# 60-hv-amp-interlock.net
KiCad netlist of a schematic drawn in EAGLE
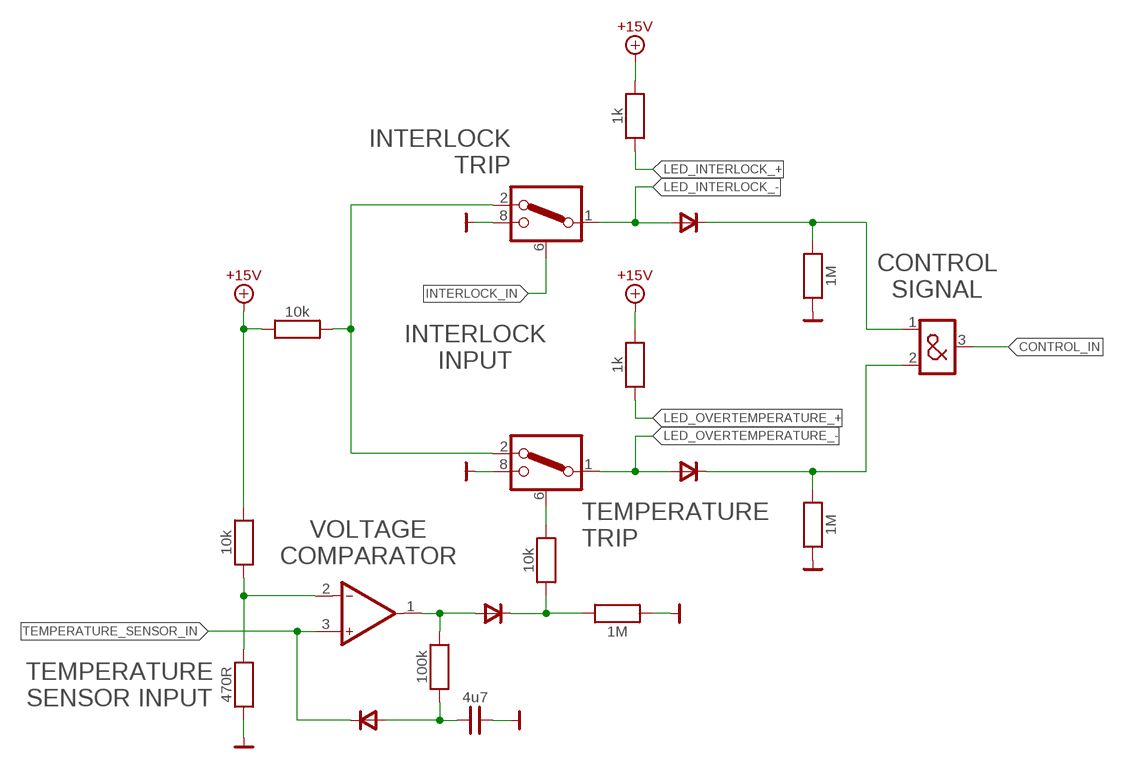
[diagram p0: schematic, sheet 1]

(export (version "E")
  (design (tool "Eeschema 10.0.6"))
  (components
    (comp (ref "C21")
      (value "4u7")
      (footprint "eagle-import:C02-MKS2-7.0-N")
      (libsource (lib "eagle-import") (part "C02-MKS2-7.0-N"))
    )
    (comp (ref "D17")
      (value "1N4148")
      (footprint "eagle-import:D04N-DO35-TYPE")
      (libsource (lib "eagle-import") (part "1N4148-04"))
    )
    (comp (ref "D21")
      (value "1N4148")
      (footprint "eagle-import:D04N-DO35-TYPE")
      (libsource (lib "eagle-import") (part "1N4148-04"))
    )
    (comp (ref "D25")
      (value "1N4148")
      (footprint "eagle-import:D04N-DO35-TYPE")
      (libsource (lib "eagle-import") (part "1N4148-04"))
    )
    (comp (ref "D26")
      (value "1N4148")
      (footprint "eagle-import:D04N-DO35-TYPE")
      (libsource (lib "eagle-import") (part "1N4148-04"))
    )
    (comp (ref "N21")
      (value "OPA4277")
      (footprint "eagle-import:DIP14L")
      (libsource (lib "eagle-import") (part "OPA4277L"))
    )
    (comp (ref "N22")
      (value "MAX4659")
      (footprint "eagle-import:DIP08L")
      (libsource (lib "eagle-import") (part "DG419L"))
    )
    (comp (ref "N23")
      (value "MAX4659")
      (footprint "eagle-import:DIP08L")
      (libsource (lib "eagle-import") (part "DG419L"))
    )
    (comp (ref "N24")
      (value "4081")
      (footprint "eagle-import:DIP14L")
      (libsource (lib "eagle-import") (part "4081L"))
    )
    (comp (ref "R1")
      (value "1M")
      (footprint "eagle-import:R04N")
      (libsource (lib "eagle-import") (part "R04"))
    )
    (comp (ref "R97")
      (value "10k")
      (footprint "eagle-import:R04N")
      (libsource (lib "eagle-import") (part "RN"))
    )
    (comp (ref "R98")
      (value "470R")
      (footprint "eagle-import:R04N")
      (libsource (lib "eagle-import") (part "RN"))
    )
    (comp (ref "R105")
      (value "100k")
      (footprint "eagle-import:R04N")
      (libsource (lib "eagle-import") (part "RN"))
    )
    (comp (ref "R109")
      (value "10k")
      (footprint "eagle-import:R04N")
      (libsource (lib "eagle-import") (part "R04"))
    )
    (comp (ref "R110")
      (value "10k")
      (footprint "eagle-import:R04N")
      (libsource (lib "eagle-import") (part "RN"))
    )
    (comp (ref "R111")
      (value "1k")
      (footprint "eagle-import:R04N")
      (libsource (lib "eagle-import") (part "R04"))
    )
    (comp (ref "R112")
      (value "1k")
      (footprint "eagle-import:R04N")
      (libsource (lib "eagle-import") (part "R04"))
    )
    (comp (ref "R150")
      (value "1M")
      (footprint "eagle-import:R04N")
      (libsource (lib "eagle-import") (part "R04"))
    )
    (comp (ref "R151")
      (value "1M")
      (footprint "eagle-import:R04N")
      (libsource (lib "eagle-import") (part "R04"))
    )
  )
  (nets
    (net (code "1") (name "CONTROL_IN") (class "Default")
      (node (ref "N24") (pin "3") (pinfunction "O_3") (pintype "output"))
    )
    (net (code "2") (name "INTERLOCK_IN") (class "Default")
      (node (ref "N22") (pin "6") (pinfunction "D_6") (pintype "input"))
    )
    (net (code "3") (name "LED_INTERLOCK_+") (class "Default")
      (node (ref "R111") (pin "1") (pinfunction "1_1") (pintype "passive"))
    )
    (net (code "4") (name "LED_INTERLOCK_-") (class "Default")
      (node (ref "D25") (pin "A") (pinfunction "A_A") (pintype "passive"))
      (node (ref "N22") (pin "1") (pinfunction "S1_1") (pintype "bidirectional"))
    )
    (net (code "5") (name "LED_OVERTEMPERATURE_+") (class "Default")
      (node (ref "R112") (pin "1") (pinfunction "1_1") (pintype "passive"))
    )
    (net (code "6") (name "LED_OVERTEMPERATURE_-") (class "Default")
      (node (ref "D26") (pin "A") (pinfunction "A_A") (pintype "passive"))
      (node (ref "N23") (pin "1") (pinfunction "S1_1") (pintype "bidirectional"))
    )
    (net (code "7") (name "Net-(C21-Pad2)") (class "Default")
      (node (ref "C21") (pin "2") (pinfunction "2_2") (pintype "passive"))
      (node (ref "D17") (pin "A") (pinfunction "A_A") (pintype "passive"))
      (node (ref "R105") (pin "1") (pinfunction "1_1") (pintype "passive"))
    )
    (net (code "8") (name "Net-(D21-PadC)") (class "Default")
      (node (ref "D21") (pin "C") (pinfunction "C_C") (pintype "passive"))
      (node (ref "R1") (pin "2") (pinfunction "2_2") (pintype "passive"))
      (node (ref "R110") (pin "1") (pinfunction "1_1") (pintype "passive"))
    )
    (net (code "9") (name "Net-(N21A-IN-)") (class "Default")
      (node (ref "N21") (pin "2") (pinfunction "IN-_2") (pintype "input"))
      (node (ref "R97") (pin "1") (pinfunction "1_1") (pintype "passive"))
      (node (ref "R98") (pin "2") (pinfunction "2_2") (pintype "passive"))
    )
    (net (code "10") (name "Net-(N21A-OUT)") (class "Default")
      (node (ref "D21") (pin "A") (pinfunction "A_A") (pintype "passive"))
      (node (ref "N21") (pin "1") (pinfunction "OUT_1") (pintype "output"))
      (node (ref "R105") (pin "2") (pinfunction "2_2") (pintype "passive"))
    )
    (net (code "11") (name "Net-(N22A-S2A)") (class "Default")
      (node (ref "N22") (pin "2") (pinfunction "S2A_2") (pintype "bidirectional"))
      (node (ref "N23") (pin "2") (pinfunction "S2A_2") (pintype "bidirectional"))
      (node (ref "R109") (pin "2") (pinfunction "2_2") (pintype "passive"))
    )
    (net (code "12") (name "Net-(N23A-D)") (class "Default")
      (node (ref "N23") (pin "6") (pinfunction "D_6") (pintype "input"))
      (node (ref "R110") (pin "2") (pinfunction "2_2") (pintype "passive"))
    )
    (net (code "13") (name "Net-(N24A-I1)") (class "Default")
      (node (ref "D25") (pin "C") (pinfunction "C_C") (pintype "passive"))
      (node (ref "N24") (pin "1") (pinfunction "I1_1") (pintype "input"))
      (node (ref "R150") (pin "2") (pinfunction "2_2") (pintype "passive"))
    )
    (net (code "14") (name "Net-(N24A-I2)") (class "Default")
      (node (ref "D26") (pin "C") (pinfunction "C_C") (pintype "passive"))
      (node (ref "N24") (pin "2") (pinfunction "I2_2") (pintype "input"))
      (node (ref "R151") (pin "2") (pinfunction "2_2") (pintype "passive"))
    )
    (net (code "15") (name "TEMPERATURE_SENSOR_IN") (class "Default")
      (node (ref "D17") (pin "C") (pinfunction "C_C") (pintype "passive"))
      (node (ref "N21") (pin "3") (pinfunction "IN+_3") (pintype "input"))
    )
    (net (code "16") (name "V+15V") (class "Default")
      (node (ref "R109") (pin "1") (pinfunction "1_1") (pintype "passive"))
      (node (ref "R111") (pin "2") (pinfunction "2_2") (pintype "passive"))
      (node (ref "R112") (pin "2") (pinfunction "2_2") (pintype "passive"))
      (node (ref "R97") (pin "2") (pinfunction "2_2") (pintype "passive"))
    )
    (net (code "17") (name "VG") (class "Default")
      (node (ref "C21") (pin "1") (pinfunction "1_1") (pintype "passive"))
      (node (ref "N22") (pin "8") (pinfunction "S2B_8") (pintype "bidirectional"))
      (node (ref "N23") (pin "8") (pinfunction "S2B_8") (pintype "bidirectional"))
      (node (ref "R1") (pin "1") (pinfunction "1_1") (pintype "passive"))
      (node (ref "R150") (pin "1") (pinfunction "1_1") (pintype "passive"))
      (node (ref "R151") (pin "1") (pinfunction "1_1") (pintype "passive"))
      (node (ref "R98") (pin "1") (pinfunction "1_1") (pintype "passive"))
    )
  )
)
